# stc8a8k64s4a12_2021-08-17.net
KiCad netlist of a schematic drawn in Altium Designer
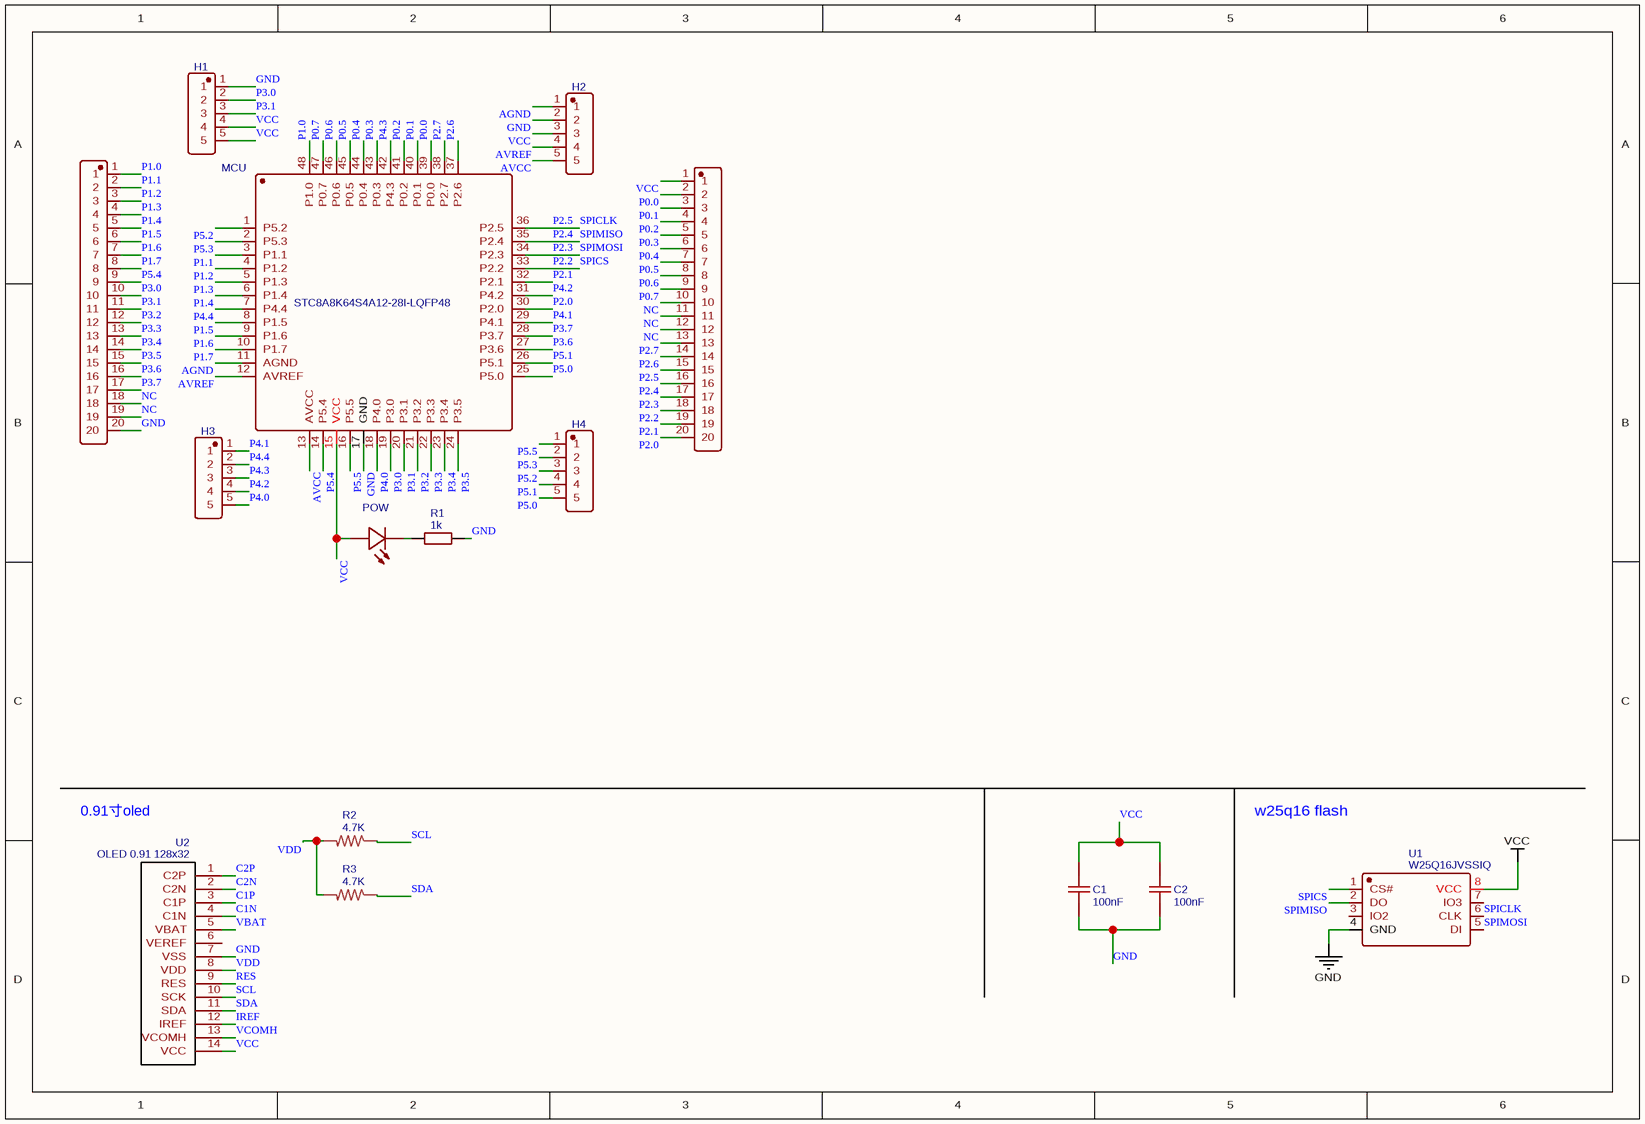
[diagram p0: stc8a8k64s4a12_2021-08-17.schdoc]

(export (version "E")
  (design (tool "Eeschema 10.0.6"))
  (components
    (comp (ref "C1")
      (value "100nF")
      (fields
        (field (name "BOM_SUPPLIER PART") "C525175")
        (field (name "BOM_MANUFACTURER PART") "FM18X104K101PBG")
        (field (name "CONTRIBUTOR") "LCSC")
      )
      (libsource (lib "altium-import") (part "root_1_100nF_"))
    )
    (comp (ref "C2")
      (value "100nF")
      (fields
        (field (name "BOM_SUPPLIER PART") "C525175")
        (field (name "BOM_MANUFACTURER PART") "FM18X104K101PBG")
        (field (name "CONTRIBUTOR") "LCSC")
      )
      (libsource (lib "altium-import") (part "root_1_100nF_"))
    )
    (comp (ref "H1")
      (value "2185-105SSNAYNT2")
      (fields (field (name "BOM_SUPPLIER PART") "C721789") (field (name "CONTRIBUTOR") "LCSC"))
      (libsource (lib "altium-import") (part "root_0_2185-105SSNAYNT2_"))
    )
    (comp (ref "H2")
      (value "2185-105SSNAYNT2")
      (fields (field (name "BOM_SUPPLIER PART") "C721789") (field (name "CONTRIBUTOR") "LCSC"))
      (libsource (lib "") (part "root_0_2185-105SSNAYNT2__1"))
    )
    (comp (ref "H3")
      (value "2185-105SSNAYNT2")
      (fields (field (name "BOM_SUPPLIER PART") "C721789") (field (name "CONTRIBUTOR") "LCSC"))
      (libsource (lib "altium-import") (part "root_0_2185-105SSNAYNT2_"))
    )
    (comp (ref "H4")
      (value "2185-105SSNAYNT2")
      (fields (field (name "BOM_SUPPLIER PART") "C721789") (field (name "CONTRIBUTOR") "LCSC"))
      (libsource (lib "") (part "root_0_2185-105SSNAYNT2__1"))
    )
    (comp (ref "J")
      (value "Header-Male-2.54_1x20")
      (fields
        (field (name "BOM_MANUFACTURER PART") "2.54mm 1*20PHeader")
        (field (name "BOM_SUPPLIER PART") "C50981")
      )
      (libsource (lib "altium-import") (part "root_0_Header-Male-2.54_1x20_"))
    )
    (comp (ref "J1")
      (value "Header-Male-2.54_1x20")
      (fields
        (field (name "BOM_MANUFACTURER PART") "2.54mm 1*20PHeader")
        (field (name "BOM_SUPPLIER PART") "C50981")
      )
      (libsource (lib "") (part "root_0_Header-Male-2.54_1x20__1"))
    )
    (comp (ref "MCU")
      (value "STC8A8K64S4A12-28I-LQFP48")
      (fields
        (field (name "BOM_SUPPLIER PART") "C84390")
        (field (name "BOM_MANUFACTURER PART") "STC8A8K64S4A12")
        (field (name "CONTRIBUTOR") "LCSC")
      )
      (libsource (lib "altium-import") (part "root_0_STC8A8K64S4A12-28I-LQFP48_"))
    )
    (comp (ref "POW")
      (value "led Green")
      (fields (field (name "BOM_SUPPLIER PART") "C14641"))
      (libsource (lib "altium-import") (part "root_2_led Green_"))
    )
    (comp (ref "R1")
      (value "1k")
      (fields
        (field (name "BOM_MANUFACTURER PART") "0603WAF1000T5E")
        (field (name "BOM_SUPPLIER PART") "C22775")
      )
      (libsource (lib "altium-import") (part "root_2_1k_"))
    )
    (comp (ref "R2")
      (value "4.7K")
      (fields (field (name "CONTRIBUTOR") "乌龟科技"))
      (libsource (lib "altium-import") (part "root_0_4.7K_"))
    )
    (comp (ref "R3")
      (value "4.7K")
      (fields (field (name "CONTRIBUTOR") "乌龟科技"))
      (libsource (lib "altium-import") (part "root_0_4.7K_"))
    )
    (comp (ref "U1")
      (value "W25Q16JVSSIQ")
      (fields
        (field (name "BOM_MANUFACTURER PART") "W25Q64JVSSIQ")
        (field (name "BOM_SUPPLIER PART") "C83140")
      )
      (libsource (lib "altium-import") (part "root_0_W25Q16JVSSIQ_"))
    )
    (comp (ref "U2")
      (value "OLED 0.91 128x32")
      (fields (field (name "CONTRIBUTOR") "davidex720"))
      (libsource (lib "altium-import") (part "root_0_OLED 0.91 128x32_"))
    )
  )
  (nets
    (net (code "1") (name "/AGND") (class "Default")
      (node (ref "H2") (pin "1") (pinfunction "1_1") (pintype "passive"))
      (node (ref "MCU") (pin "11") (pinfunction "AGND_11") (pintype "passive"))
    )
    (net (code "2") (name "/AVCC") (class "Default")
      (node (ref "H2") (pin "5") (pinfunction "5_5") (pintype "passive"))
      (node (ref "MCU") (pin "13") (pinfunction "AVCC_13") (pintype "passive"))
    )
    (net (code "3") (name "/AVREF") (class "Default")
      (node (ref "H2") (pin "4") (pinfunction "4_4") (pintype "passive"))
      (node (ref "MCU") (pin "12") (pinfunction "AVREF_12") (pintype "passive"))
    )
    (net (code "4") (name "/C1N") (class "Default")
      (node (ref "U2") (pin "4") (pinfunction "C1N_4") (pintype "passive"))
    )
    (net (code "5") (name "/C1P") (class "Default")
      (node (ref "U2") (pin "3") (pinfunction "C1P_3") (pintype "passive"))
    )
    (net (code "6") (name "/C2N") (class "Default")
      (node (ref "U2") (pin "2") (pinfunction "C2N_2") (pintype "passive"))
    )
    (net (code "7") (name "/C2P") (class "Default")
      (node (ref "U2") (pin "1") (pinfunction "C2P_1") (pintype "passive"))
    )
    (net (code "8") (name "/IREF") (class "Default")
      (node (ref "U2") (pin "12") (pinfunction "IREF_12") (pintype "passive"))
    )
    (net (code "9") (name "/NC") (class "Default")
      (node (ref "J") (pin "10") (pinfunction "10_10") (pintype "passive"))
      (node (ref "J") (pin "11") (pinfunction "11_11") (pintype "passive"))
      (node (ref "J") (pin "12") (pinfunction "12_12") (pintype "passive"))
      (node (ref "J1") (pin "18") (pinfunction "18_18") (pintype "passive"))
      (node (ref "J1") (pin "19") (pinfunction "19_19") (pintype "passive"))
    )
    (net (code "10") (name "/P0.0") (class "Default")
      (node (ref "J") (pin "2") (pinfunction "2_2") (pintype "passive"))
      (node (ref "MCU") (pin "39") (pinfunction "P0.0_39") (pintype "passive"))
    )
    (net (code "11") (name "/P0.1") (class "Default")
      (node (ref "J") (pin "3") (pinfunction "3_3") (pintype "passive"))
      (node (ref "MCU") (pin "40") (pinfunction "P0.1_40") (pintype "passive"))
    )
    (net (code "12") (name "/P0.2") (class "Default")
      (node (ref "J") (pin "4") (pinfunction "4_4") (pintype "passive"))
      (node (ref "MCU") (pin "41") (pinfunction "P0.2_41") (pintype "passive"))
    )
    (net (code "13") (name "/P0.3") (class "Default")
      (node (ref "J") (pin "5") (pinfunction "5_5") (pintype "passive"))
      (node (ref "MCU") (pin "43") (pinfunction "P0.3_43") (pintype "passive"))
    )
    (net (code "14") (name "/P0.4") (class "Default")
      (node (ref "J") (pin "6") (pinfunction "6_6") (pintype "passive"))
      (node (ref "MCU") (pin "44") (pinfunction "P0.4_44") (pintype "passive"))
    )
    (net (code "15") (name "/P0.5") (class "Default")
      (node (ref "J") (pin "7") (pinfunction "7_7") (pintype "passive"))
      (node (ref "MCU") (pin "45") (pinfunction "P0.5_45") (pintype "passive"))
    )
    (net (code "16") (name "/P0.6") (class "Default")
      (node (ref "J") (pin "8") (pinfunction "8_8") (pintype "passive"))
      (node (ref "MCU") (pin "46") (pinfunction "P0.6_46") (pintype "passive"))
    )
    (net (code "17") (name "/P0.7") (class "Default")
      (node (ref "J") (pin "9") (pinfunction "9_9") (pintype "passive"))
      (node (ref "MCU") (pin "47") (pinfunction "P0.7_47") (pintype "passive"))
    )
    (net (code "18") (name "/P1.0") (class "Default")
      (node (ref "J1") (pin "1") (pinfunction "1_1") (pintype "passive"))
      (node (ref "MCU") (pin "48") (pinfunction "P1.0_48") (pintype "passive"))
    )
    (net (code "19") (name "/P1.1") (class "Default")
      (node (ref "J1") (pin "2") (pinfunction "2_2") (pintype "passive"))
      (node (ref "MCU") (pin "3") (pinfunction "P1.1_3") (pintype "passive"))
    )
    (net (code "20") (name "/P1.2") (class "Default")
      (node (ref "J1") (pin "3") (pinfunction "3_3") (pintype "passive"))
      (node (ref "MCU") (pin "4") (pinfunction "P1.2_4") (pintype "passive"))
    )
    (net (code "21") (name "/P1.3") (class "Default")
      (node (ref "J1") (pin "4") (pinfunction "4_4") (pintype "passive"))
      (node (ref "MCU") (pin "5") (pinfunction "P1.3_5") (pintype "passive"))
    )
    (net (code "22") (name "/P1.4") (class "Default")
      (node (ref "J1") (pin "5") (pinfunction "5_5") (pintype "passive"))
      (node (ref "MCU") (pin "6") (pinfunction "P1.4_6") (pintype "passive"))
    )
    (net (code "23") (name "/P1.5") (class "Default")
      (node (ref "J1") (pin "6") (pinfunction "6_6") (pintype "passive"))
      (node (ref "MCU") (pin "8") (pinfunction "P1.5_8") (pintype "passive"))
    )
    (net (code "24") (name "/P1.6") (class "Default")
      (node (ref "J1") (pin "7") (pinfunction "7_7") (pintype "passive"))
      (node (ref "MCU") (pin "9") (pinfunction "P1.6_9") (pintype "passive"))
    )
    (net (code "25") (name "/P1.7") (class "Default")
      (node (ref "J1") (pin "8") (pinfunction "8_8") (pintype "passive"))
      (node (ref "MCU") (pin "10") (pinfunction "P1.7_10") (pintype "passive"))
    )
    (net (code "26") (name "/P2.0") (class "Default")
      (node (ref "J") (pin "20") (pinfunction "20_20") (pintype "passive"))
      (node (ref "MCU") (pin "30") (pinfunction "P2.0_30") (pintype "passive"))
    )
    (net (code "27") (name "/P2.1") (class "Default")
      (node (ref "J") (pin "19") (pinfunction "19_19") (pintype "passive"))
      (node (ref "MCU") (pin "32") (pinfunction "P2.1_32") (pintype "passive"))
    )
    (net (code "28") (name "/P2.2") (class "Default")
      (node (ref "J") (pin "18") (pinfunction "18_18") (pintype "passive"))
      (node (ref "MCU") (pin "33") (pinfunction "P2.2_33") (pintype "passive"))
      (node (ref "U1") (pin "1") (pinfunction "CS#_1") (pintype "passive"))
    )
    (net (code "29") (name "/P2.3") (class "Default")
      (node (ref "J") (pin "17") (pinfunction "17_17") (pintype "passive"))
      (node (ref "MCU") (pin "34") (pinfunction "P2.3_34") (pintype "passive"))
      (node (ref "U1") (pin "5") (pinfunction "DI_5") (pintype "passive"))
    )
    (net (code "30") (name "/P2.4") (class "Default")
      (node (ref "J") (pin "16") (pinfunction "16_16") (pintype "passive"))
      (node (ref "MCU") (pin "35") (pinfunction "P2.4_35") (pintype "passive"))
      (node (ref "U1") (pin "2") (pinfunction "DO_2") (pintype "passive"))
    )
    (net (code "31") (name "/P2.5") (class "Default")
      (node (ref "J") (pin "15") (pinfunction "15_15") (pintype "passive"))
      (node (ref "MCU") (pin "36") (pinfunction "P2.5_36") (pintype "passive"))
      (node (ref "U1") (pin "6") (pinfunction "CLK_6") (pintype "passive"))
    )
    (net (code "32") (name "/P2.6") (class "Default")
      (node (ref "J") (pin "14") (pinfunction "14_14") (pintype "passive"))
      (node (ref "MCU") (pin "37") (pinfunction "P2.6_37") (pintype "passive"))
    )
    (net (code "33") (name "/P2.7") (class "Default")
      (node (ref "J") (pin "13") (pinfunction "13_13") (pintype "passive"))
      (node (ref "MCU") (pin "38") (pinfunction "P2.7_38") (pintype "passive"))
    )
    (net (code "34") (name "/P3.0") (class "Default")
      (node (ref "H1") (pin "2") (pinfunction "2_2") (pintype "passive"))
      (node (ref "J1") (pin "10") (pinfunction "10_10") (pintype "passive"))
      (node (ref "MCU") (pin "19") (pinfunction "P3.0_19") (pintype "passive"))
    )
    (net (code "35") (name "/P3.1") (class "Default")
      (node (ref "H1") (pin "3") (pinfunction "3_3") (pintype "passive"))
      (node (ref "J1") (pin "11") (pinfunction "11_11") (pintype "passive"))
      (node (ref "MCU") (pin "20") (pinfunction "P3.1_20") (pintype "passive"))
    )
    (net (code "36") (name "/P3.2") (class "Default")
      (node (ref "J1") (pin "12") (pinfunction "12_12") (pintype "passive"))
      (node (ref "MCU") (pin "21") (pinfunction "P3.2_21") (pintype "passive"))
    )
    (net (code "37") (name "/P3.3") (class "Default")
      (node (ref "J1") (pin "13") (pinfunction "13_13") (pintype "passive"))
      (node (ref "MCU") (pin "22") (pinfunction "P3.3_22") (pintype "passive"))
    )
    (net (code "38") (name "/P3.4") (class "Default")
      (node (ref "J1") (pin "14") (pinfunction "14_14") (pintype "passive"))
      (node (ref "MCU") (pin "23") (pinfunction "P3.4_23") (pintype "passive"))
    )
    (net (code "39") (name "/P3.5") (class "Default")
      (node (ref "J1") (pin "15") (pinfunction "15_15") (pintype "passive"))
      (node (ref "MCU") (pin "24") (pinfunction "P3.5_24") (pintype "passive"))
    )
    (net (code "40") (name "/P3.6") (class "Default")
      (node (ref "J1") (pin "16") (pinfunction "16_16") (pintype "passive"))
      (node (ref "MCU") (pin "27") (pinfunction "P3.6_27") (pintype "passive"))
    )
    (net (code "41") (name "/P3.7") (class "Default")
      (node (ref "J1") (pin "17") (pinfunction "17_17") (pintype "passive"))
      (node (ref "MCU") (pin "28") (pinfunction "P3.7_28") (pintype "passive"))
    )
    (net (code "42") (name "/P4.0") (class "Default")
      (node (ref "H3") (pin "5") (pinfunction "5_5") (pintype "passive"))
      (node (ref "MCU") (pin "18") (pinfunction "P4.0_18") (pintype "passive"))
    )
    (net (code "43") (name "/P4.1") (class "Default")
      (node (ref "H3") (pin "1") (pinfunction "1_1") (pintype "passive"))
      (node (ref "MCU") (pin "29") (pinfunction "P4.1_29") (pintype "passive"))
    )
    (net (code "44") (name "/P4.2") (class "Default")
      (node (ref "H3") (pin "4") (pinfunction "4_4") (pintype "passive"))
      (node (ref "MCU") (pin "31") (pinfunction "P4.2_31") (pintype "passive"))
    )
    (net (code "45") (name "/P4.3") (class "Default")
      (node (ref "H3") (pin "3") (pinfunction "3_3") (pintype "passive"))
      (node (ref "MCU") (pin "42") (pinfunction "P4.3_42") (pintype "passive"))
    )
    (net (code "46") (name "/P4.4") (class "Default")
      (node (ref "H3") (pin "2") (pinfunction "2_2") (pintype "passive"))
      (node (ref "MCU") (pin "7") (pinfunction "P4.4_7") (pintype "passive"))
    )
    (net (code "47") (name "/P5.0") (class "Default")
      (node (ref "H4") (pin "5") (pinfunction "5_5") (pintype "passive"))
      (node (ref "MCU") (pin "25") (pinfunction "P5.0_25") (pintype "passive"))
    )
    (net (code "48") (name "/P5.1") (class "Default")
      (node (ref "H4") (pin "4") (pinfunction "4_4") (pintype "passive"))
      (node (ref "MCU") (pin "26") (pinfunction "P5.1_26") (pintype "passive"))
    )
    (net (code "49") (name "/P5.2") (class "Default")
      (node (ref "H4") (pin "3") (pinfunction "3_3") (pintype "passive"))
      (node (ref "MCU") (pin "1") (pinfunction "P5.2_1") (pintype "passive"))
    )
    (net (code "50") (name "/P5.3") (class "Default")
      (node (ref "H4") (pin "2") (pinfunction "2_2") (pintype "passive"))
      (node (ref "MCU") (pin "2") (pinfunction "P5.3_2") (pintype "passive"))
    )
    (net (code "51") (name "/P5.4") (class "Default")
      (node (ref "J1") (pin "9") (pinfunction "9_9") (pintype "passive"))
      (node (ref "MCU") (pin "14") (pinfunction "P5.4_14") (pintype "passive"))
    )
    (net (code "52") (name "/P5.5") (class "Default")
      (node (ref "H4") (pin "1") (pinfunction "1_1") (pintype "passive"))
      (node (ref "MCU") (pin "16") (pinfunction "P5.5_16") (pintype "passive"))
    )
    (net (code "53") (name "/RES") (class "Default")
      (node (ref "U2") (pin "9") (pinfunction "RES_9") (pintype "passive"))
    )
    (net (code "54") (name "/SCL") (class "Default")
      (node (ref "R2") (pin "1") (pinfunction "1_1") (pintype "passive"))
      (node (ref "U2") (pin "10") (pinfunction "SCK_10") (pintype "passive"))
    )
    (net (code "55") (name "/SDA") (class "Default")
      (node (ref "R3") (pin "1") (pinfunction "1_1") (pintype "passive"))
      (node (ref "U2") (pin "11") (pinfunction "SDA_11") (pintype "passive"))
    )
    (net (code "56") (name "/VBAT") (class "Default")
      (node (ref "U2") (pin "5") (pinfunction "VBAT_5") (pintype "passive"))
    )
    (net (code "57") (name "/VCOMH") (class "Default")
      (node (ref "U2") (pin "13") (pinfunction "VCOMH_13") (pintype "passive"))
    )
    (net (code "58") (name "/VDD") (class "Default")
      (node (ref "R2") (pin "2") (pinfunction "2_2") (pintype "passive"))
      (node (ref "R3") (pin "2") (pinfunction "2_2") (pintype "passive"))
      (node (ref "U2") (pin "8") (pinfunction "VDD_8") (pintype "passive"))
    )
    (net (code "59") (name "GND") (class "Default")
      (node (ref "C1") (pin "1") (pinfunction "1_1") (pintype "passive"))
      (node (ref "C2") (pin "1") (pinfunction "1_1") (pintype "passive"))
      (node (ref "H1") (pin "1") (pinfunction "1_1") (pintype "passive"))
      (node (ref "H2") (pin "2") (pinfunction "2_2") (pintype "passive"))
      (node (ref "J1") (pin "20") (pinfunction "20_20") (pintype "passive"))
      (node (ref "MCU") (pin "17") (pinfunction "GND_17") (pintype "passive"))
      (node (ref "R1") (pin "1") (pinfunction "1_1") (pintype "passive"))
      (node (ref "U1") (pin "4") (pinfunction "GND_4") (pintype "passive"))
      (node (ref "U2") (pin "7") (pinfunction "VSS_7") (pintype "passive"))
    )
    (net (code "60") (name "Net-(POW--)") (class "Default")
      (node (ref "POW") (pin "1") (pinfunction "-_1") (pintype "passive"))
      (node (ref "R1") (pin "2") (pinfunction "2_2") (pintype "passive"))
    )
    (net (code "61") (name "VCC") (class "Default")
      (node (ref "C1") (pin "2") (pinfunction "2_2") (pintype "passive"))
      (node (ref "C2") (pin "2") (pinfunction "2_2") (pintype "passive"))
      (node (ref "H1") (pin "4") (pinfunction "4_4") (pintype "passive"))
      (node (ref "H1") (pin "5") (pinfunction "5_5") (pintype "passive"))
      (node (ref "H2") (pin "3") (pinfunction "3_3") (pintype "passive"))
      (node (ref "J") (pin "1") (pinfunction "1_1") (pintype "passive"))
      (node (ref "MCU") (pin "15") (pinfunction "VCC_15") (pintype "passive"))
      (node (ref "POW") (pin "2") (pinfunction "+_2") (pintype "passive"))
      (node (ref "U1") (pin "8") (pinfunction "VCC_8") (pintype "passive"))
      (node (ref "U2") (pin "14") (pinfunction "VCC_14") (pintype "passive"))
    )
    (net (code "62") (name "unconnected-(U1-IO2-Pad3)") (class "Default")
      (node (ref "U1") (pin "3") (pinfunction "IO2_3") (pintype "passive"))
    )
    (net (code "63") (name "unconnected-(U1-IO3-Pad7)") (class "Default")
      (node (ref "U1") (pin "7") (pinfunction "IO3_7") (pintype "passive"))
    )
    (net (code "64") (name "unconnected-(U2-VEREF-Pad6)") (class "Default")
      (node (ref "U2") (pin "6") (pinfunction "VEREF_6") (pintype "passive"))
    )
  )
)
